# demeter.net
KiCad netlist of a schematic drawn in EAGLE
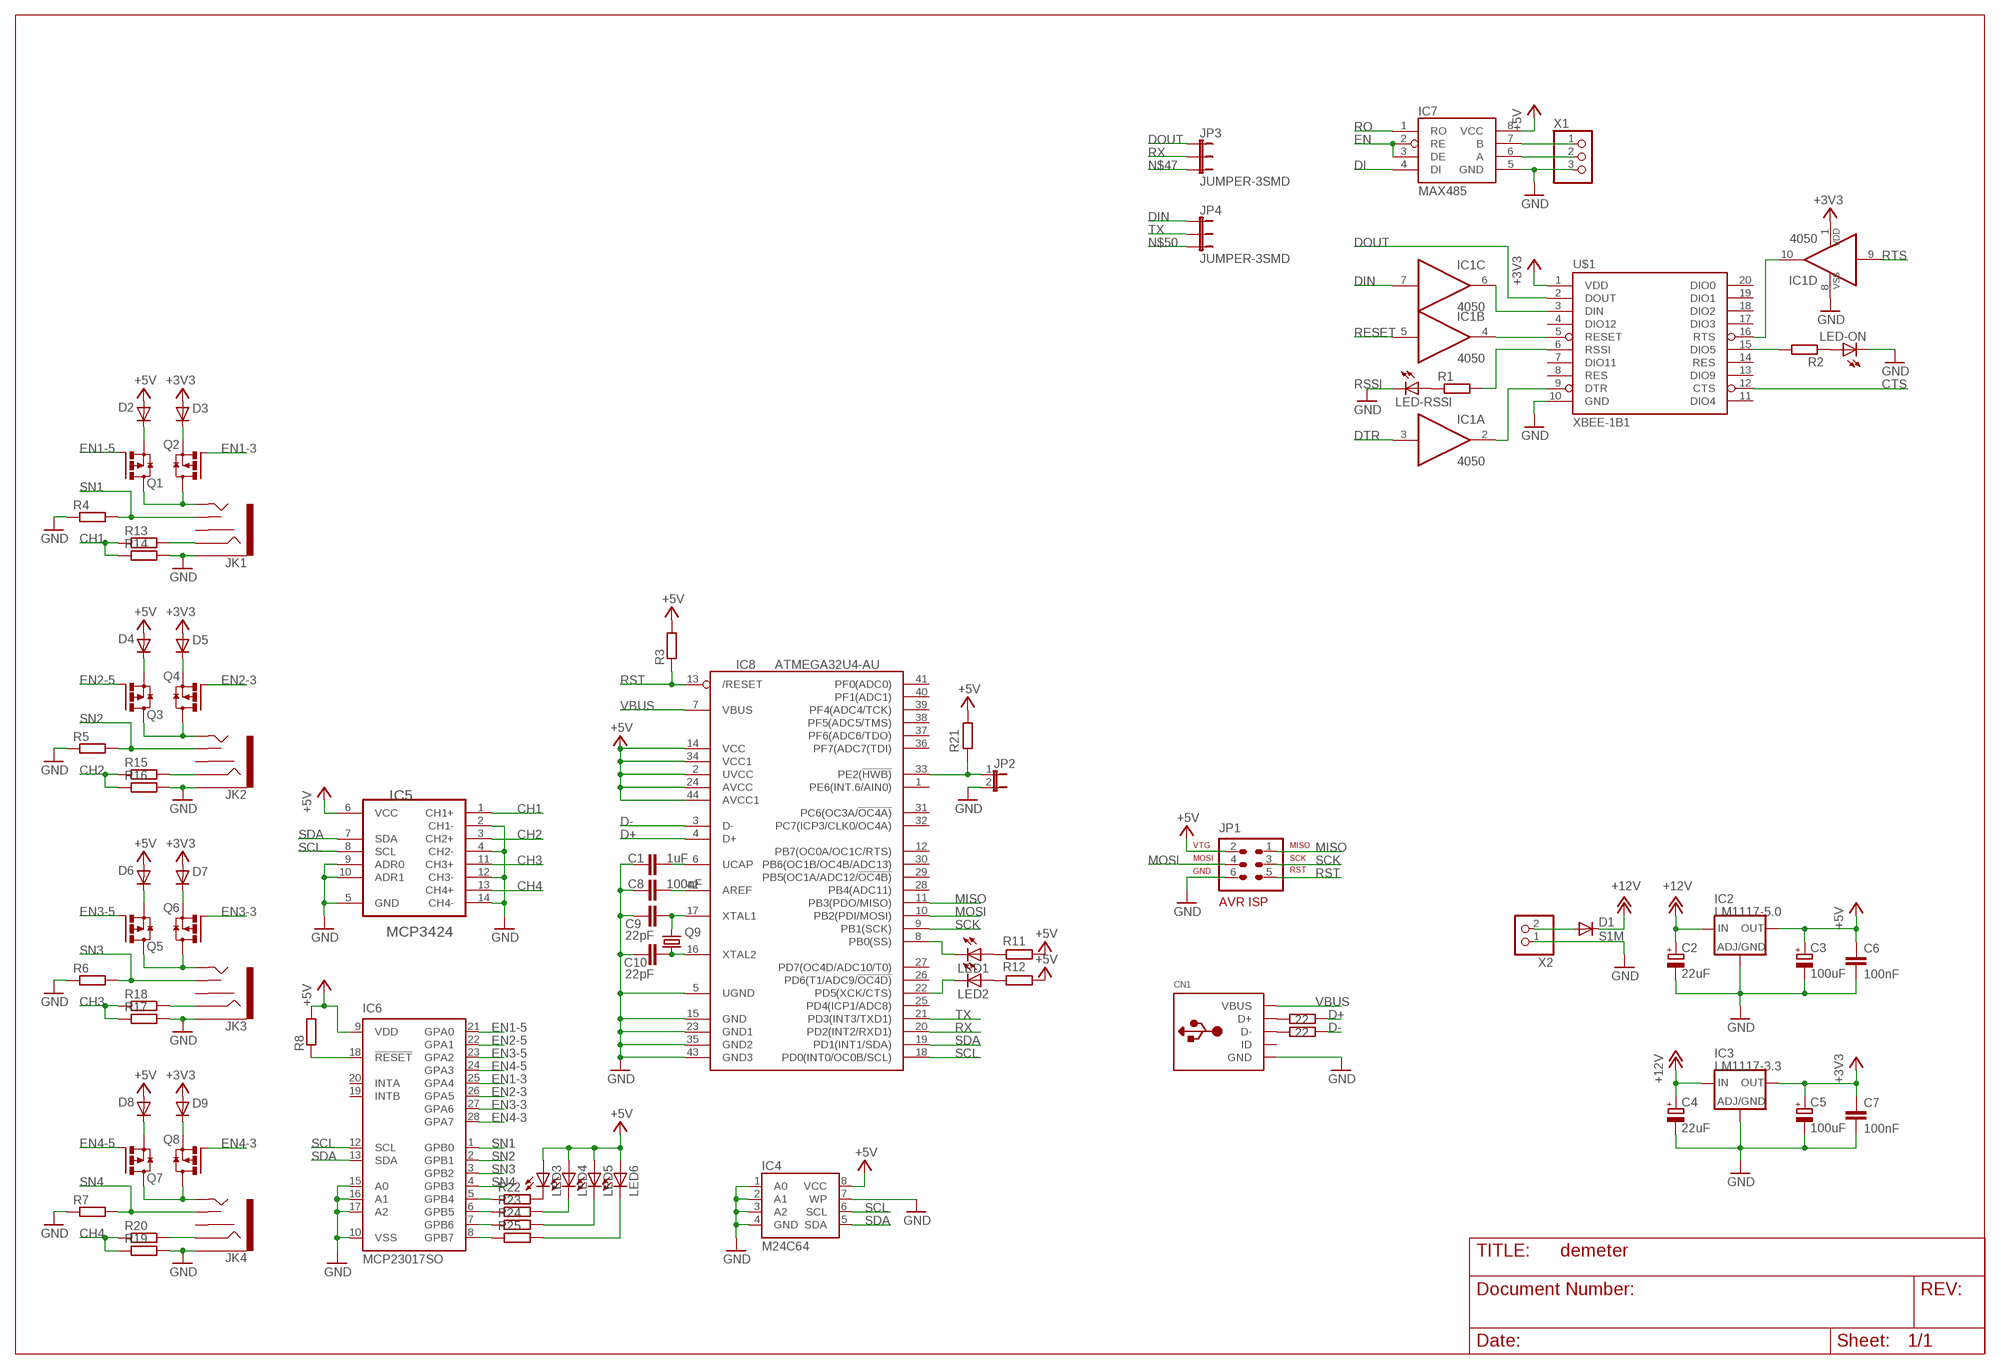
[diagram p0: schematic, sheet 1]

(export (version "E")
  (design (tool "Eeschema 10.0.6"))
  (components
    (comp (ref "C1")
      (value "1uF")
      (footprint "eagle-import:C0805K")
      (libsource (lib "eagle-import") (part "C-EUC0805K"))
    )
    (comp (ref "C2")
      (value "22uF")
      (footprint "eagle-import:PANASONIC_D")
      (libsource (lib "eagle-import") (part "CPOL-EUPD"))
    )
    (comp (ref "C3")
      (value "100uF")
      (footprint "eagle-import:PANASONIC_D")
      (libsource (lib "eagle-import") (part "CPOL-EUPD"))
    )
    (comp (ref "C4")
      (value "22uF")
      (footprint "eagle-import:PANASONIC_D")
      (libsource (lib "eagle-import") (part "CPOL-EUPD"))
    )
    (comp (ref "C5")
      (value "100uF")
      (footprint "eagle-import:PANASONIC_D")
      (libsource (lib "eagle-import") (part "CPOL-EUPD"))
    )
    (comp (ref "C6")
      (value "100nF")
      (footprint "eagle-import:C0805K")
      (libsource (lib "eagle-import") (part "C-EUC0805K"))
    )
    (comp (ref "C7")
      (value "100nF")
      (footprint "eagle-import:C0805K")
      (libsource (lib "eagle-import") (part "C-EUC0805K"))
    )
    (comp (ref "C8")
      (value "100nF")
      (footprint "eagle-import:C0805K")
      (libsource (lib "eagle-import") (part "C-EUC0805K"))
    )
    (comp (ref "C9")
      (value "22pF")
      (footprint "eagle-import:C0805K")
      (libsource (lib "eagle-import") (part "C-EUC0805K"))
    )
    (comp (ref "C10")
      (value "22pF")
      (footprint "eagle-import:C0805K")
      (libsource (lib "eagle-import") (part "C-EUC0805K"))
    )
    (comp (ref "CN1")
      (value "USBMINIB")
      (footprint "eagle-import:USB-MINIB")
      (libsource (lib "eagle-import") (part "USBMINIB"))
    )
    (comp (ref "D1")
      (value "S1M")
      (footprint "eagle-import:DO-214AC")
      (libsource (lib "eagle-import") (part "S1M"))
    )
    (comp (ref "D2")
      (value "MBR0520")
      (footprint "eagle-import:SOD123")
      (libsource (lib "eagle-import") (part "MBR0520"))
    )
    (comp (ref "D3")
      (value "MBR0520")
      (footprint "eagle-import:SOD123")
      (libsource (lib "eagle-import") (part "MBR0520"))
    )
    (comp (ref "D4")
      (value "MBR0520")
      (footprint "eagle-import:SOD123")
      (libsource (lib "eagle-import") (part "MBR0520"))
    )
    (comp (ref "D5")
      (value "MBR0520")
      (footprint "eagle-import:SOD123")
      (libsource (lib "eagle-import") (part "MBR0520"))
    )
    (comp (ref "D6")
      (value "MBR0520")
      (footprint "eagle-import:SOD123")
      (libsource (lib "eagle-import") (part "MBR0520"))
    )
    (comp (ref "D7")
      (value "MBR0520")
      (footprint "eagle-import:SOD123")
      (libsource (lib "eagle-import") (part "MBR0520"))
    )
    (comp (ref "D8")
      (value "MBR0520")
      (footprint "eagle-import:SOD123")
      (libsource (lib "eagle-import") (part "MBR0520"))
    )
    (comp (ref "D9")
      (value "MBR0520")
      (footprint "eagle-import:SOD123")
      (libsource (lib "eagle-import") (part "MBR0520"))
    )
    (comp (ref "IC1")
      (value "4050")
      (footprint "eagle-import:SO16")
      (libsource (lib "eagle-import") (part "4050D"))
    )
    (comp (ref "IC2")
      (value "LM1117-5.0")
      (footprint "eagle-import:DPACK")
      (libsource (lib "eagle-import") (part "LM1117DT"))
    )
    (comp (ref "IC3")
      (value "LM1117-3.3")
      (footprint "eagle-import:DPACK")
      (libsource (lib "eagle-import") (part "LM1117DT"))
    )
    (comp (ref "IC4")
      (value "M24C64")
      (footprint "eagle-import:SO08")
      (libsource (lib "eagle-import") (part "AT24C"))
    )
    (comp (ref "IC5")
      (value "MCP3424")
      (footprint "eagle-import:SO14")
      (fields (field (name "MPN") "MCP3424-E/SL"))
      (libsource (lib "eagle-import") (part "MCP3424"))
    )
    (comp (ref "IC6")
      (value "MCP23017SO")
      (footprint "eagle-import:SO28W")
      (fields (field (name "MF") "MICROCHIP") (field (name "MPN") "MCP23017-E/SO"))
      (libsource (lib "eagle-import") (part "MCP23017SO"))
    )
    (comp (ref "IC7")
      (value "MAX485")
      (footprint "eagle-import:SO08")
      (libsource (lib "eagle-import") (part "MAX485"))
    )
    (comp (ref "IC8")
      (value "ATMEGA32U4-AU")
      (footprint "eagle-import:TQFP44")
      (libsource (lib "eagle-import") (part "ATMEGA32U4-AU"))
    )
    (comp (ref "JK1")
      (value "AUDIO-JACK2PTH")
      (footprint "eagle-import:AUDIO-JACK")
      (libsource (lib "eagle-import") (part "AUDIO-JACK2PTH"))
    )
    (comp (ref "JK2")
      (value "AUDIO-JACK2PTH")
      (footprint "eagle-import:AUDIO-JACK")
      (libsource (lib "eagle-import") (part "AUDIO-JACK2PTH"))
    )
    (comp (ref "JK3")
      (value "AUDIO-JACK2PTH")
      (footprint "eagle-import:AUDIO-JACK")
      (libsource (lib "eagle-import") (part "AUDIO-JACK2PTH"))
    )
    (comp (ref "JK4")
      (value "AUDIO-JACK2PTH")
      (footprint "eagle-import:AUDIO-JACK")
      (libsource (lib "eagle-import") (part "AUDIO-JACK2PTH"))
    )
    (comp (ref "JP1")
      (value "AVR-ISP-6")
      (footprint "eagle-import:AVR-ISP-6")
      (libsource (lib "eagle-import") (part "AVR-ISP-6"))
    )
    (comp (ref "JP2")
      (value "JUMPER-2SMD-NO")
      (footprint "eagle-import:SJ_2S-NO")
      (libsource (lib "eagle-import") (part "JUMPER-2SMD-NO"))
    )
    (comp (ref "JP3")
      (value "JUMPER-3SMD")
      (footprint "eagle-import:SJ_3")
      (libsource (lib "eagle-import") (part "JUMPER-3SMD"))
    )
    (comp (ref "JP4")
      (value "JUMPER-3SMD")
      (footprint "eagle-import:SJ_3")
      (libsource (lib "eagle-import") (part "JUMPER-3SMD"))
    )
    (comp (ref "LED-ON")
      (value "LED3MM")
      (footprint "eagle-import:LED3MM")
      (libsource (lib "eagle-import") (part "LED3MM"))
    )
    (comp (ref "LED-RSSI")
      (value "LED3MM")
      (footprint "eagle-import:LED3MM")
      (libsource (lib "eagle-import") (part "LED3MM"))
    )
    (comp (ref "LED1")
      (value "LED0805")
      (footprint "eagle-import:CHIP-LED0805")
      (libsource (lib "eagle-import") (part "mark_2_LED0805"))
    )
    (comp (ref "LED2")
      (value "LED0805")
      (footprint "eagle-import:CHIP-LED0805")
      (libsource (lib "eagle-import") (part "mark_2_LED0805"))
    )
    (comp (ref "LED3")
      (value "LED0805")
      (footprint "eagle-import:CHIP-LED0805")
      (libsource (lib "eagle-import") (part "mark_2_LED0805"))
    )
    (comp (ref "LED4")
      (value "LED0805")
      (footprint "eagle-import:CHIP-LED0805")
      (libsource (lib "eagle-import") (part "mark_2_LED0805"))
    )
    (comp (ref "LED5")
      (value "LED0805")
      (footprint "eagle-import:CHIP-LED0805")
      (libsource (lib "eagle-import") (part "mark_2_LED0805"))
    )
    (comp (ref "LED6")
      (value "LED0805")
      (footprint "eagle-import:CHIP-LED0805")
      (libsource (lib "eagle-import") (part "mark_2_LED0805"))
    )
    (comp (ref "Q1")
      (value "IRLML6402")
      (footprint "eagle-import:SOT23")
      (libsource (lib "eagle-import") (part "IRLML6402"))
    )
    (comp (ref "Q2")
      (value "IRLML6402")
      (footprint "eagle-import:SOT23")
      (libsource (lib "eagle-import") (part "IRLML6402"))
    )
    (comp (ref "Q3")
      (value "IRLML6402")
      (footprint "eagle-import:SOT23")
      (libsource (lib "eagle-import") (part "IRLML6402"))
    )
    (comp (ref "Q4")
      (value "IRLML6402")
      (footprint "eagle-import:SOT23")
      (libsource (lib "eagle-import") (part "IRLML6402"))
    )
    (comp (ref "Q5")
      (value "IRLML6402")
      (footprint "eagle-import:SOT23")
      (libsource (lib "eagle-import") (part "IRLML6402"))
    )
    (comp (ref "Q6")
      (value "IRLML6402")
      (footprint "eagle-import:SOT23")
      (libsource (lib "eagle-import") (part "IRLML6402"))
    )
    (comp (ref "Q7")
      (value "IRLML6402")
      (footprint "eagle-import:SOT23")
      (libsource (lib "eagle-import") (part "IRLML6402"))
    )
    (comp (ref "Q8")
      (value "IRLML6402")
      (footprint "eagle-import:SOT23")
      (libsource (lib "eagle-import") (part "IRLML6402"))
    )
    (comp (ref "Q9")
      (value "CRYSTALHC49UP")
      (footprint "eagle-import:HC49UP")
      (libsource (lib "eagle-import") (part "CRYSTALHC49UP"))
    )
    (comp (ref "R1")
      (value "R-EU_R0805")
      (footprint "eagle-import:R0805")
      (libsource (lib "eagle-import") (part "R-EU_R0805"))
    )
    (comp (ref "R2")
      (value "R-EU_R0805")
      (footprint "eagle-import:R0805")
      (libsource (lib "eagle-import") (part "R-EU_R0805"))
    )
    (comp (ref "R3")
      (value "R-EU_R0805")
      (footprint "eagle-import:R0805")
      (libsource (lib "eagle-import") (part "R-EU_R0805"))
    )
    (comp (ref "R4")
      (value "R-EU_R0805")
      (footprint "eagle-import:R0805")
      (libsource (lib "eagle-import") (part "R-EU_R0805"))
    )
    (comp (ref "R5")
      (value "R-EU_R0805")
      (footprint "eagle-import:R0805")
      (libsource (lib "eagle-import") (part "R-EU_R0805"))
    )
    (comp (ref "R6")
      (value "R-EU_R0805")
      (footprint "eagle-import:R0805")
      (libsource (lib "eagle-import") (part "R-EU_R0805"))
    )
    (comp (ref "R7")
      (value "R-EU_R0805")
      (footprint "eagle-import:R0805")
      (libsource (lib "eagle-import") (part "R-EU_R0805"))
    )
    (comp (ref "R8")
      (value "R-EU_R0805")
      (footprint "eagle-import:R0805")
      (libsource (lib "eagle-import") (part "R-EU_R0805"))
    )
    (comp (ref "R9")
      (value "22")
      (footprint "eagle-import:R0805")
      (libsource (lib "eagle-import") (part "R-EU_R0805"))
    )
    (comp (ref "R10")
      (value "22")
      (footprint "eagle-import:R0805")
      (libsource (lib "eagle-import") (part "R-EU_R0805"))
    )
    (comp (ref "R11")
      (value "R-EU_R0805")
      (footprint "eagle-import:R0805")
      (libsource (lib "eagle-import") (part "R-EU_R0805"))
    )
    (comp (ref "R12")
      (value "R-EU_R0805")
      (footprint "eagle-import:R0805")
      (libsource (lib "eagle-import") (part "R-EU_R0805"))
    )
    (comp (ref "R13")
      (value "R-EU_R0805")
      (footprint "eagle-import:R0805")
      (libsource (lib "eagle-import") (part "R-EU_R0805"))
    )
    (comp (ref "R14")
      (value "R-EU_R0805")
      (footprint "eagle-import:R0805")
      (libsource (lib "eagle-import") (part "R-EU_R0805"))
    )
    (comp (ref "R15")
      (value "R-EU_R0805")
      (footprint "eagle-import:R0805")
      (libsource (lib "eagle-import") (part "R-EU_R0805"))
    )
    (comp (ref "R16")
      (value "R-EU_R0805")
      (footprint "eagle-import:R0805")
      (libsource (lib "eagle-import") (part "R-EU_R0805"))
    )
    (comp (ref "R17")
      (value "R-EU_R0805")
      (footprint "eagle-import:R0805")
      (libsource (lib "eagle-import") (part "R-EU_R0805"))
    )
    (comp (ref "R18")
      (value "R-EU_R0805")
      (footprint "eagle-import:R0805")
      (libsource (lib "eagle-import") (part "R-EU_R0805"))
    )
    (comp (ref "R19")
      (value "R-EU_R0805")
      (footprint "eagle-import:R0805")
      (libsource (lib "eagle-import") (part "R-EU_R0805"))
    )
    (comp (ref "R20")
      (value "R-EU_R0805")
      (footprint "eagle-import:R0805")
      (libsource (lib "eagle-import") (part "R-EU_R0805"))
    )
    (comp (ref "R21")
      (value "R-EU_R0805")
      (footprint "eagle-import:R0805")
      (libsource (lib "eagle-import") (part "R-EU_R0805"))
    )
    (comp (ref "R22")
      (value "R-EU_R0805")
      (footprint "eagle-import:R0805")
      (libsource (lib "eagle-import") (part "R-EU_R0805"))
    )
    (comp (ref "R23")
      (value "R-EU_R0805")
      (footprint "eagle-import:R0805")
      (libsource (lib "eagle-import") (part "R-EU_R0805"))
    )
    (comp (ref "R24")
      (value "R-EU_R0805")
      (footprint "eagle-import:R0805")
      (libsource (lib "eagle-import") (part "R-EU_R0805"))
    )
    (comp (ref "R25")
      (value "R-EU_R0805")
      (footprint "eagle-import:R0805")
      (libsource (lib "eagle-import") (part "R-EU_R0805"))
    )
    (comp (ref "U$1")
      (value "XBEE-1B1")
      (footprint "eagle-import:XBEE-1")
      (libsource (lib "eagle-import") (part "XBEE-1B1"))
    )
    (comp (ref "X1")
      (value "W237-103")
      (footprint "eagle-import:W237-103")
      (libsource (lib "eagle-import") (part "W237-103"))
    )
    (comp (ref "X2")
      (value "W237-102")
      (footprint "eagle-import:W237-102")
      (libsource (lib "eagle-import") (part "W237-102"))
    )
  )
  (nets
    (net (code "1") (name "+3V3") (class "Default")
      (node (ref "C5") (pin "+") (pinfunction "+_+") (pintype "passive"))
      (node (ref "C7") (pin "1") (pinfunction "1_1") (pintype "passive"))
      (node (ref "D3") (pin "A") (pinfunction "A_A") (pintype "passive"))
      (node (ref "D5") (pin "A") (pinfunction "A_A") (pintype "passive"))
      (node (ref "D7") (pin "A") (pinfunction "A_A") (pintype "passive"))
      (node (ref "D9") (pin "A") (pinfunction "A_A") (pintype "passive"))
      (node (ref "IC1") (pin "1") (pinfunction "VDD_1") (pintype "power_in"))
      (node (ref "IC3") (pin "4") (pinfunction "OUT_4") (pintype "passive"))
      (node (ref "U$1") (pin "1") (pinfunction "VDD_1") (pintype "power_in"))
    )
    (net (code "2") (name "+5V") (class "Default")
      (node (ref "C3") (pin "+") (pinfunction "+_+") (pintype "passive"))
      (node (ref "C6") (pin "1") (pinfunction "1_1") (pintype "passive"))
      (node (ref "D2") (pin "A") (pinfunction "A_A") (pintype "passive"))
      (node (ref "D4") (pin "A") (pinfunction "A_A") (pintype "passive"))
      (node (ref "D6") (pin "A") (pinfunction "A_A") (pintype "passive"))
      (node (ref "D8") (pin "A") (pinfunction "A_A") (pintype "passive"))
      (node (ref "IC2") (pin "4") (pinfunction "OUT_4") (pintype "passive"))
      (node (ref "IC4") (pin "8") (pinfunction "VCC_8") (pintype "power_in"))
      (node (ref "IC5") (pin "6") (pinfunction "VCC_6") (pintype "power_in"))
      (node (ref "IC6") (pin "9") (pinfunction "VDD_9") (pintype "power_in"))
      (node (ref "IC7") (pin "8") (pinfunction "VCC_8") (pintype "bidirectional"))
      (node (ref "IC8") (pin "14") (pinfunction "VCC_14") (pintype "bidirectional"))
      (node (ref "IC8") (pin "2") (pinfunction "UVCC_2") (pintype "bidirectional"))
      (node (ref "IC8") (pin "24") (pinfunction "AVCC_24") (pintype "bidirectional"))
      (node (ref "IC8") (pin "34") (pinfunction "VCC1_34") (pintype "bidirectional"))
      (node (ref "IC8") (pin "44") (pinfunction "AVCC1_44") (pintype "bidirectional"))
      (node (ref "JP1") (pin "2") (pinfunction "VTG_2") (pintype "passive"))
      (node (ref "LED3") (pin "A") (pinfunction "A_A") (pintype "passive"))
      (node (ref "LED4") (pin "A") (pinfunction "A_A") (pintype "passive"))
      (node (ref "LED5") (pin "A") (pinfunction "A_A") (pintype "passive"))
      (node (ref "LED6") (pin "A") (pinfunction "A_A") (pintype "passive"))
      (node (ref "R11") (pin "1") (pinfunction "1_1") (pintype "passive"))
      (node (ref "R12") (pin "1") (pinfunction "1_1") (pintype "passive"))
      (node (ref "R21") (pin "1") (pinfunction "1_1") (pintype "passive"))
      (node (ref "R3") (pin "2") (pinfunction "2_2") (pintype "passive"))
      (node (ref "R8") (pin "2") (pinfunction "2_2") (pintype "passive"))
    )
    (net (code "3") (name "+12V") (class "Default")
      (node (ref "C2") (pin "+") (pinfunction "+_+") (pintype "passive"))
      (node (ref "C4") (pin "+") (pinfunction "+_+") (pintype "passive"))
      (node (ref "D1") (pin "C") (pinfunction "C_C") (pintype "passive"))
      (node (ref "IC2") (pin "3") (pinfunction "IN_3") (pintype "input"))
      (node (ref "IC3") (pin "3") (pinfunction "IN_3") (pintype "input"))
    )
    (net (code "4") (name "/CH1") (class "Default")
      (node (ref "IC5") (pin "1") (pinfunction "CH1+_1") (pintype "input"))
      (node (ref "R13") (pin "1") (pinfunction "1_1") (pintype "passive"))
      (node (ref "R14") (pin "1") (pinfunction "1_1") (pintype "passive"))
    )
    (net (code "5") (name "/CH2") (class "Default")
      (node (ref "IC5") (pin "3") (pinfunction "CH2+_3") (pintype "input"))
      (node (ref "R15") (pin "1") (pinfunction "1_1") (pintype "passive"))
      (node (ref "R16") (pin "1") (pinfunction "1_1") (pintype "passive"))
    )
    (net (code "6") (name "/CH3") (class "Default")
      (node (ref "IC5") (pin "11") (pinfunction "CH3+_11") (pintype "input"))
      (node (ref "R17") (pin "1") (pinfunction "1_1") (pintype "passive"))
      (node (ref "R18") (pin "1") (pinfunction "1_1") (pintype "passive"))
    )
    (net (code "7") (name "/CH4") (class "Default")
      (node (ref "IC5") (pin "13") (pinfunction "CH4+_13") (pintype "input"))
      (node (ref "R19") (pin "1") (pinfunction "1_1") (pintype "passive"))
      (node (ref "R20") (pin "1") (pinfunction "1_1") (pintype "passive"))
    )
    (net (code "8") (name "/CTS") (class "Default")
      (node (ref "U$1") (pin "12") (pinfunction "CTS_12") (pintype "output"))
    )
    (net (code "9") (name "/D+") (class "Default")
      (node (ref "IC8") (pin "4") (pinfunction "D+_4") (pintype "bidirectional"))
      (node (ref "R9") (pin "1") (pinfunction "1_1") (pintype "passive"))
    )
    (net (code "10") (name "/D-") (class "Default")
      (node (ref "IC8") (pin "3") (pinfunction "D-_3") (pintype "bidirectional"))
      (node (ref "R10") (pin "1") (pinfunction "1_1") (pintype "passive"))
    )
    (net (code "11") (name "/DI") (class "Default")
      (node (ref "IC7") (pin "4") (pinfunction "DI_4") (pintype "bidirectional"))
    )
    (net (code "12") (name "/DIN") (class "Default")
      (node (ref "IC1") (pin "7") (pinfunction "I_7") (pintype "input"))
      (node (ref "JP4") (pin "1") (pinfunction "1_1") (pintype "passive"))
    )
    (net (code "13") (name "/DOUT") (class "Default")
      (node (ref "JP3") (pin "1") (pinfunction "1_1") (pintype "passive"))
      (node (ref "U$1") (pin "2") (pinfunction "DOUT_2") (pintype "output"))
    )
    (net (code "14") (name "/DTR") (class "Default")
      (node (ref "IC1") (pin "3") (pinfunction "I_3") (pintype "input"))
    )
    (net (code "15") (name "/EN") (class "Default")
      (node (ref "IC7") (pin "2") (pinfunction "RE_2") (pintype "bidirectional"))
      (node (ref "IC7") (pin "3") (pinfunction "DE_3") (pintype "bidirectional"))
    )
    (net (code "16") (name "/EN1-3") (class "Default")
      (node (ref "IC6") (pin "25") (pinfunction "GPA4_25") (pintype "bidirectional"))
      (node (ref "Q2") (pin "1") (pinfunction "G_1") (pintype "passive"))
    )
    (net (code "17") (name "/EN1-5") (class "Default")
      (node (ref "IC6") (pin "21") (pinfunction "GPA0_21") (pintype "bidirectional"))
      (node (ref "Q1") (pin "1") (pinfunction "G_1") (pintype "passive"))
    )
    (net (code "18") (name "/EN2-3") (class "Default")
      (node (ref "IC6") (pin "26") (pinfunction "GPA5_26") (pintype "bidirectional"))
      (node (ref "Q4") (pin "1") (pinfunction "G_1") (pintype "passive"))
    )
    (net (code "19") (name "/EN2-5") (class "Default")
      (node (ref "IC6") (pin "22") (pinfunction "GPA1_22") (pintype "bidirectional"))
      (node (ref "Q3") (pin "1") (pinfunction "G_1") (pintype "passive"))
    )
    (net (code "20") (name "/EN3-3") (class "Default")
      (node (ref "IC6") (pin "27") (pinfunction "GPA6_27") (pintype "bidirectional"))
      (node (ref "Q6") (pin "1") (pinfunction "G_1") (pintype "passive"))
    )
    (net (code "21") (name "/EN3-5") (class "Default")
      (node (ref "IC6") (pin "23") (pinfunction "GPA2_23") (pintype "bidirectional"))
      (node (ref "Q5") (pin "1") (pinfunction "G_1") (pintype "passive"))
    )
    (net (code "22") (name "/EN4-3") (class "Default")
      (node (ref "IC6") (pin "28") (pinfunction "GPA7_28") (pintype "bidirectional"))
      (node (ref "Q8") (pin "1") (pinfunction "G_1") (pintype "passive"))
    )
    (net (code "23") (name "/EN4-5") (class "Default")
      (node (ref "IC6") (pin "24") (pinfunction "GPA3_24") (pintype "bidirectional"))
      (node (ref "Q7") (pin "1") (pinfunction "G_1") (pintype "passive"))
    )
    (net (code "24") (name "/MISO") (class "Default")
      (node (ref "IC8") (pin "11") (pinfunction "PB3(PDO/MISO)_11") (pintype "bidirectional"))
      (node (ref "JP1") (pin "1") (pinfunction "MISO_1") (pintype "passive"))
    )
    (net (code "25") (name "/MOSI") (class "Default")
      (node (ref "IC8") (pin "10") (pinfunction "PB2(PDI/MOSI)_10") (pintype "bidirectional"))
      (node (ref "JP1") (pin "4") (pinfunction "MOSI_4") (pintype "passive"))
    )
    (net (code "26") (name "/N$47") (class "Default")
      (node (ref "JP3") (pin "3") (pinfunction "3_3") (pintype "passive"))
    )
    (net (code "27") (name "/N$50") (class "Default")
      (node (ref "JP4") (pin "3") (pinfunction "3_3") (pintype "passive"))
    )
    (net (code "28") (name "/RESET") (class "Default")
      (node (ref "IC1") (pin "5") (pinfunction "I_5") (pintype "input"))
    )
    (net (code "29") (name "/RO") (class "Default")
      (node (ref "IC7") (pin "1") (pinfunction "RO_1") (pintype "bidirectional"))
    )
    (net (code "30") (name "/RSSI") (class "Default")
      (node (ref "R1") (pin "2") (pinfunction "2_2") (pintype "passive"))
      (node (ref "U$1") (pin "6") (pinfunction "RSSI_6") (pintype "bidirectional"))
    )
    (net (code "31") (name "/RST") (class "Default")
      (node (ref "IC8") (pin "13") (pinfunction "/RESET_13") (pintype "bidirectional"))
      (node (ref "JP1") (pin "5") (pinfunction "RST_5") (pintype "passive"))
      (node (ref "R3") (pin "1") (pinfunction "1_1") (pintype "passive"))
    )
    (net (code "32") (name "/RTS") (class "Default")
      (node (ref "IC1") (pin "9") (pinfunction "I_9") (pintype "input"))
    )
    (net (code "33") (name "/RX") (class "Default")
      (node (ref "IC8") (pin "20") (pinfunction "PD2(INT2/RXD1)_20") (pintype "bidirectional"))
      (node (ref "JP3") (pin "2") (pinfunction "2_2") (pintype "passive"))
    )
    (net (code "34") (name "/SCK") (class "Default")
      (node (ref "IC8") (pin "9") (pinfunction "PB1(SCK)_9") (pintype "bidirectional"))
      (node (ref "JP1") (pin "3") (pinfunction "SCK_3") (pintype "passive"))
    )
    (net (code "35") (name "/SCL") (class "Default")
      (node (ref "IC4") (pin "6") (pinfunction "SCL_6") (pintype "bidirectional"))
      (node (ref "IC5") (pin "8") (pinfunction "SCL_8") (pintype "input"))
      (node (ref "IC6") (pin "12") (pinfunction "SCL_12") (pintype "input"))
      (node (ref "IC8") (pin "18") (pinfunction "PD0(INT0/OC0B/SCL)_18") (pintype "bidirectional"))
    )
    (net (code "36") (name "/SDA") (class "Default")
      (node (ref "IC4") (pin "5") (pinfunction "SDA_5") (pintype "bidirectional"))
      (node (ref "IC5") (pin "7") (pinfunction "SDA_7") (pintype "bidirectional"))
      (node (ref "IC6") (pin "13") (pinfunction "SDA_13") (pintype "bidirectional"))
      (node (ref "IC8") (pin "19") (pinfunction "PD1(INT1/SDA)_19") (pintype "bidirectional"))
    )
    (net (code "37") (name "/SN1") (class "Default")
      (node (ref "IC6") (pin "1") (pinfunction "GPB0_1") (pintype "bidirectional"))
      (node (ref "JK1") (pin "TSH") (pinfunction "TSH_TSH") (pintype "bidirectional"))
      (node (ref "R4") (pin "2") (pinfunction "2_2") (pintype "passive"))
    )
    (net (code "38") (name "/SN2") (class "Default")
      (node (ref "IC6") (pin "2") (pinfunction "GPB1_2") (pintype "bidirectional"))
      (node (ref "JK2") (pin "TSH") (pinfunction "TSH_TSH") (pintype "bidirectional"))
      (node (ref "R5") (pin "2") (pinfunction "2_2") (pintype "passive"))
    )
    (net (code "39") (name "/SN3") (class "Default")
      (node (ref "IC6") (pin "3") (pinfunction "GPB2_3") (pintype "bidirectional"))
      (node (ref "JK3") (pin "TSH") (pinfunction "TSH_TSH") (pintype "bidirectional"))
      (node (ref "R6") (pin "2") (pinfunction "2_2") (pintype "passive"))
    )
    (net (code "40") (name "/SN4") (class "Default")
      (node (ref "IC6") (pin "4") (pinfunction "GPB3_4") (pintype "bidirectional"))
      (node (ref "JK4") (pin "TSH") (pinfunction "TSH_TSH") (pintype "bidirectional"))
      (node (ref "R7") (pin "2") (pinfunction "2_2") (pintype "passive"))
    )
    (net (code "41") (name "/TX") (class "Default")
      (node (ref "IC8") (pin "21") (pinfunction "PD3(INT3/TXD1)_21") (pintype "bidirectional"))
      (node (ref "JP4") (pin "2") (pinfunction "2_2") (pintype "passive"))
    )
    (net (code "42") (name "/VBUS") (class "Default")
      (node (ref "CN1") (pin "VBUS") (pinfunction "VBUS_VBUS") (pintype "power_in"))
      (node (ref "IC8") (pin "7") (pinfunction "VBUS_7") (pintype "bidirectional"))
    )
    (net (code "43") (name "GND") (class "Default")
      (node (ref "C1") (pin "2") (pinfunction "2_2") (pintype "passive"))
      (node (ref "C10") (pin "2") (pinfunction "2_2") (pintype "passive"))
      (node (ref "C2") (pin "-") (pinfunction "-_-") (pintype "passive"))
      (node (ref "C3") (pin "-") (pinfunction "-_-") (pintype "passive"))
      (node (ref "C4") (pin "-") (pinfunction "-_-") (pintype "passive"))
      (node (ref "C5") (pin "-") (pinfunction "-_-") (pintype "passive"))
      (node (ref "C6") (pin "2") (pinfunction "2_2") (pintype "passive"))
      (node (ref "C7") (pin "2") (pinfunction "2_2") (pintype "passive"))
      (node (ref "C8") (pin "2") (pinfunction "2_2") (pintype "passive"))
      (node (ref "C9") (pin "2") (pinfunction "2_2") (pintype "passive"))
      (node (ref "CN1") (pin "GND") (pinfunction "GND_GND") (pintype "power_in"))
      (node (ref "IC1") (pin "8") (pinfunction "VSS_8") (pintype "power_in"))
      (node (ref "IC2") (pin "1") (pinfunction "ADJ_1") (pintype "input"))
      (node (ref "IC3") (pin "1") (pinfunction "ADJ_1") (pintype "input"))
      (node (ref "IC4") (pin "1") (pinfunction "A0_1") (pintype "input"))
      (node (ref "IC4") (pin "2") (pinfunction "A1_2") (pintype "input"))
      (node (ref "IC4") (pin "3") (pinfunction "A2_3") (pintype "input"))
      (node (ref "IC4") (pin "4") (pinfunction "GND_4") (pintype "power_in"))
      (node (ref "IC4") (pin "7") (pinfunction "WP_7") (pintype "input"))
      (node (ref "IC5") (pin "10") (pinfunction "ADR1_10") (pintype "input"))
      (node (ref "IC5") (pin "12") (pinfunction "CH3-_12") (pintype "input"))
      (node (ref "IC5") (pin "14") (pinfunction "CH4-_14") (pintype "input"))
      (node (ref "IC5") (pin "2") (pinfunction "CH1-_2") (pintype "input"))
      (node (ref "IC5") (pin "4") (pinfunction "CH2-_4") (pintype "input"))
      (node (ref "IC5") (pin "5") (pinfunction "GND_5") (pintype "power_in"))
      (node (ref "IC5") (pin "9") (pinfunction "ADR0_9") (pintype "input"))
      (node (ref "IC6") (pin "10") (pinfunction "VSS_10") (pintype "power_in"))
      (node (ref "IC6") (pin "15") (pinfunction "A0_15") (pintype "input"))
      (node (ref "IC6") (pin "16") (pinfunction "A1_16") (pintype "input"))
      (node (ref "IC6") (pin "17") (pinfunction "A2_17") (pintype "input"))
      (node (ref "IC7") (pin "5") (pinfunction "GND_5") (pintype "bidirectional"))
      (node (ref "IC8") (pin "15") (pinfunction "GND_15") (pintype "bidirectional"))
      (node (ref "IC8") (pin "23") (pinfunction "GND1_23") (pintype "bidirectional"))
      (node (ref "IC8") (pin "35") (pinfunction "GND2_35") (pintype "bidirectional"))
      (node (ref "IC8") (pin "43") (pinfunction "GND3_43") (pintype "bidirectional"))
      (node (ref "IC8") (pin "5") (pinfunction "UGND_5") (pintype "bidirectional"))
      (node (ref "JK1") (pin "SLEEVE") (pinfunction "SLEEVE_SLEEVE") (pintype "bidirectional"))
      (node (ref "JK2") (pin "SLEEVE") (pinfunction "SLEEVE_SLEEVE") (pintype "bidirectional"))
      (node (ref "JK3") (pin "SLEEVE") (pinfunction "SLEEVE_SLEEVE") (pintype "bidirectional"))
      (node (ref "JK4") (pin "SLEEVE") (pinfunction "SLEEVE_SLEEVE") (pintype "bidirectional"))
      (node (ref "JP1") (pin "6") (pinfunction "GND_6") (pintype "passive"))
      (node (ref "JP2") (pin "2") (pinfunction "2_2") (pintype "passive"))
      (node (ref "LED-ON") (pin "K") (pinfunction "C_K") (pintype "passive"))
      (node (ref "LED-RSSI") (pin "K") (pinfunction "C_K") (pintype "passive"))
      (node (ref "R14") (pin "2") (pinfunction "2_2") (pintype "passive"))
      (node (ref "R16") (pin "2") (pinfunction "2_2") (pintype "passive"))
      (node (ref "R17") (pin "2") (pinfunction "2_2") (pintype "passive"))
      (node (ref "R19") (pin "2") (pinfunction "2_2") (pintype "passive"))
      (node (ref "R4") (pin "1") (pinfunction "1_1") (pintype "passive"))
      (node (ref "R5") (pin "1") (pinfunction "1_1") (pintype "passive"))
      (node (ref "R6") (pin "1") (pinfunction "1_1") (pintype "passive"))
      (node (ref "R7") (pin "1") (pinfunction "1_1") (pintype "passive"))
      (node (ref "U$1") (pin "10") (pinfunction "GND_10") (pintype "power_in"))
      (node (ref "X1") (pin "3") (pinfunction "3_3") (pintype "passive"))
      (node (ref "X2") (pin "1") (pinfunction "1_1") (pintype "passive"))
    )
    (net (code "44") (name "Net-(CN1-PadD+)") (class "Default")
      (node (ref "CN1") (pin "D+") (pinfunction "D+_D+") (pintype "bidirectional"))
      (node (ref "R9") (pin "2") (pinfunction "2_2") (pintype "passive"))
    )
    (net (code "45") (name "Net-(CN1-PadD-)") (class "Default")
      (node (ref "CN1") (pin "D-") (pinfunction "D-_D-") (pintype "bidirectional"))
      (node (ref "R10") (pin "2") (pinfunction "2_2") (pintype "passive"))
    )
    (net (code "46") (name "Net-(D1-PadA)") (class "Default")
      (node (ref "D1") (pin "A") (pinfunction "A_A") (pintype "passive"))
      (node (ref "X2") (pin "2") (pinfunction "2_2") (pintype "passive"))
    )
    (net (code "47") (name "Net-(IC1A-O)") (class "Default")
      (node (ref "IC1") (pin "2") (pinfunction "O_2") (pintype "output"))
      (node (ref "U$1") (pin "9") (pinfunction "DTR_9") (pintype "bidirectional"))
    )
    (net (code "48") (name "Net-(IC1B-O)") (class "Default")
      (node (ref "IC1") (pin "4") (pinfunction "O_4") (pintype "output"))
      (node (ref "U$1") (pin "5") (pinfunction "RESET_5") (pintype "input"))
    )
    (net (code "49") (name "Net-(IC1C-O)") (class "Default")
      (node (ref "IC1") (pin "6") (pinfunction "O_6") (pintype "output"))
      (node (ref "U$1") (pin "3") (pinfunction "DIN_3") (pintype "input"))
    )
    (net (code "50") (name "Net-(IC1D-O)") (class "Default")
      (node (ref "IC1") (pin "10") (pinfunction "O_10") (pintype "output"))
      (node (ref "U$1") (pin "16") (pinfunction "RTS_16") (pintype "input"))
    )
    (net (code "51") (name "Net-(IC6-GPB4)") (class "Default")
      (node (ref "IC6") (pin "5") (pinfunction "GPB4_5") (pintype "bidirectional"))
      (node (ref "R22") (pin "1") (pinfunction "1_1") (pintype "passive"))
    )
    (net (code "52") (name "Net-(IC6-GPB5)") (class "Default")
      (node (ref "IC6") (pin "6") (pinfunction "GPB5_6") (pintype "bidirectional"))
      (node (ref "R23") (pin "1") (pinfunction "1_1") (pintype "passive"))
    )
    (net (code "53") (name "Net-(IC6-GPB6)") (class "Default")
      (node (ref "IC6") (pin "7") (pinfunction "GPB6_7") (pintype "bidirectional"))
      (node (ref "R24") (pin "1") (pinfunction "1_1") (pintype "passive"))
    )
    (net (code "54") (name "Net-(IC6-GPB7)") (class "Default")
      (node (ref "IC6") (pin "8") (pinfunction "GPB7_8") (pintype "bidirectional"))
      (node (ref "R25") (pin "1") (pinfunction "1_1") (pintype "passive"))
    )
    (net (code "55") (name "Net-(IC6-~{RESET})") (class "Default")
      (node (ref "IC6") (pin "18") (pinfunction "~{RESET}_18") (pintype "input"))
      (node (ref "R8") (pin "1") (pinfunction "1_1") (pintype "passive"))
    )
    (net (code "56") (name "Net-(IC7-A)") (class "Default")
      (node (ref "IC7") (pin "6") (pinfunction "A_6") (pintype "bidirectional"))
      (node (ref "X1") (pin "2") (pinfunction "2_2") (pintype "passive"))
    )
    (net (code "57") (name "Net-(IC7-B)") (class "Default")
      (node (ref "IC7") (pin "7") (pinfunction "B_7") (pintype "bidirectional"))
      (node (ref "X1") (pin "1") (pinfunction "1_1") (pintype "passive"))
    )
    (net (code "58") (name "Net-(IC8-AREF)") (class "Default")
      (node (ref "C8") (pin "1") (pinfunction "1_1") (pintype "passive"))
      (node (ref "IC8") (pin "42") (pinfunction "AREF_42") (pintype "bidirectional"))
    )
    (net (code "59") (name "Net-(IC8-PB0(SS))") (class "Default")
      (node (ref "IC8") (pin "8") (pinfunction "PB0(SS)_8") (pintype "bidirectional"))
      (node (ref "LED1") (pin "C") (pinfunction "C_C") (pintype "passive"))
    )
    (net (code "60") (name "Net-(IC8-PD5(XCK{slash}CTS))") (class "Default")
      (node (ref "IC8") (pin "22") (pinfunction "PD5(XCK/CTS)_22") (pintype "bidirectional"))
      (node (ref "LED2") (pin "C") (pinfunction "C_C") (pintype "passive"))
    )
    (net (code "61") (name "Net-(IC8-PE2(~{HWB}))") (class "Default")
      (node (ref "IC8") (pin "33") (pinfunction "PE2(~{HWB})_33") (pintype "bidirectional"))
      (node (ref "JP2") (pin "1") (pinfunction "1_1") (pintype "passive"))
      (node (ref "R21") (pin "2") (pinfunction "2_2") (pintype "passive"))
    )
    (net (code "62") (name "Net-(IC8-UCAP)") (class "Default")
      (node (ref "C1") (pin "1") (pinfunction "1_1") (pintype "passive"))
      (node (ref "IC8") (pin "6") (pinfunction "UCAP_6") (pintype "bidirectional"))
    )
    (net (code "63") (name "Net-(IC8-XTAL1)") (class "Default")
      (node (ref "C9") (pin "1") (pinfunction "1_1") (pintype "passive"))
      (node (ref "IC8") (pin "17") (pinfunction "XTAL1_17") (pintype "bidirectional"))
      (node (ref "Q9") (pin "2") (pinfunction "2_2") (pintype "passive"))
    )
    (net (code "64") (name "Net-(IC8-XTAL2)") (class "Default")
      (node (ref "C10") (pin "1") (pinfunction "1_1") (pintype "passive"))
      (node (ref "IC8") (pin "16") (pinfunction "XTAL2_16") (pintype "bidirectional"))
      (node (ref "Q9") (pin "1") (pinfunction "1_1") (pintype "passive"))
    )
    (net (code "65") (name "Net-(JK1-PadRING)") (class "Default")
      (node (ref "JK1") (pin "RING") (pinfunction "RING_RING") (pintype "bidirectional"))
      (node (ref "R13") (pin "2") (pinfunction "2_2") (pintype "passive"))
    )
    (net (code "66") (name "Net-(JK2-PadRING)") (class "Default")
      (node (ref "JK2") (pin "RING") (pinfunction "RING_RING") (pintype "bidirectional"))
      (node (ref "R15") (pin "2") (pinfunction "2_2") (pintype "passive"))
    )
    (net (code "67") (name "Net-(JK3-PadRING)") (class "Default")
      (node (ref "JK3") (pin "RING") (pinfunction "RING_RING") (pintype "bidirectional"))
      (node (ref "R18") (pin "2") (pinfunction "2_2") (pintype "passive"))
    )
    (net (code "68") (name "Net-(JK4-PadRING)") (class "Default")
      (node (ref "JK4") (pin "RING") (pinfunction "RING_RING") (pintype "bidirectional"))
      (node (ref "R20") (pin "2") (pinfunction "2_2") (pintype "passive"))
    )
    (net (code "69") (name "Net-(LED-ON-PadA)") (class "Default")
      (node (ref "LED-ON") (pin "A") (pinfunction "A_A") (pintype "passive"))
      (node (ref "R2") (pin "1") (pinfunction "1_1") (pintype "passive"))
    )
    (net (code "70") (name "Net-(LED-RSSI-PadA)") (class "Default")
      (node (ref "LED-RSSI") (pin "A") (pinfunction "A_A") (pintype "passive"))
      (node (ref "R1") (pin "1") (pinfunction "1_1") (pintype "passive"))
    )
    (net (code "71") (name "Net-(LED1-PadA)") (class "Default")
      (node (ref "LED1") (pin "A") (pinfunction "A_A") (pintype "passive"))
      (node (ref "R11") (pin "2") (pinfunction "2_2") (pintype "passive"))
    )
    (net (code "72") (name "Net-(LED2-PadA)") (class "Default")
      (node (ref "LED2") (pin "A") (pinfunction "A_A") (pintype "passive"))
      (node (ref "R12") (pin "2") (pinfunction "2_2") (pintype "passive"))
    )
    (net (code "73") (name "Net-(LED3-PadC)") (class "Default")
      (node (ref "LED3") (pin "C") (pinfunction "C_C") (pintype "passive"))
      (node (ref "R22") (pin "2") (pinfunction "2_2") (pintype "passive"))
    )
    (net (code "74") (name "Net-(LED4-PadC)") (class "Default")
      (node (ref "LED4") (pin "C") (pinfunction "C_C") (pintype "passive"))
      (node (ref "R23") (pin "2") (pinfunction "2_2") (pintype "passive"))
    )
    (net (code "75") (name "Net-(LED5-PadC)") (class "Default")
      (node (ref "LED5") (pin "C") (pinfunction "C_C") (pintype "passive"))
      (node (ref "R24") (pin "2") (pinfunction "2_2") (pintype "passive"))
    )
    (net (code "76") (name "Net-(LED6-PadC)") (class "Default")
      (node (ref "LED6") (pin "C") (pinfunction "C_C") (pintype "passive"))
      (node (ref "R25") (pin "2") (pinfunction "2_2") (pintype "passive"))
    )
    (net (code "77") (name "Net-(Q1-D)") (class "Default")
      (node (ref "JK1") (pin "TIP") (pinfunction "TIP_TIP") (pintype "bidirectional"))
      (node (ref "Q1") (pin "3") (pinfunction "D_3") (pintype "passive"))
      (node (ref "Q2") (pin "3") (pinfunction "D_3") (pintype "passive"))
    )
    (net (code "78") (name "Net-(Q1-S)") (class "Default")
      (node (ref "D2") (pin "C") (pinfunction "C_C") (pintype "passive"))
      (node (ref "Q1") (pin "2") (pinfunction "S_2") (pintype "passive"))
    )
    (net (code "79") (name "Net-(Q2-S)") (class "Default")
      (node (ref "D3") (pin "C") (pinfunction "C_C") (pintype "passive"))
      (node (ref "Q2") (pin "2") (pinfunction "S_2") (pintype "passive"))
    )
    (net (code "80") (name "Net-(Q3-D)") (class "Default")
      (node (ref "JK2") (pin "TIP") (pinfunction "TIP_TIP") (pintype "bidirectional"))
      (node (ref "Q3") (pin "3") (pinfunction "D_3") (pintype "passive"))
      (node (ref "Q4") (pin "3") (pinfunction "D_3") (pintype "passive"))
    )
    (net (code "81") (name "Net-(Q3-S)") (class "Default")
      (node (ref "D4") (pin "C") (pinfunction "C_C") (pintype "passive"))
      (node (ref "Q3") (pin "2") (pinfunction "S_2") (pintype "passive"))
    )
    (net (code "82") (name "Net-(Q4-S)") (class "Default")
      (node (ref "D5") (pin "C") (pinfunction "C_C") (pintype "passive"))
      (node (ref "Q4") (pin "2") (pinfunction "S_2") (pintype "passive"))
    )
    (net (code "83") (name "Net-(Q5-D)") (class "Default")
      (node (ref "JK3") (pin "TIP") (pinfunction "TIP_TIP") (pintype "bidirectional"))
      (node (ref "Q5") (pin "3") (pinfunction "D_3") (pintype "passive"))
      (node (ref "Q6") (pin "3") (pinfunction "D_3") (pintype "passive"))
    )
    (net (code "84") (name "Net-(Q5-S)") (class "Default")
      (node (ref "D6") (pin "C") (pinfunction "C_C") (pintype "passive"))
      (node (ref "Q5") (pin "2") (pinfunction "S_2") (pintype "passive"))
    )
    (net (code "85") (name "Net-(Q6-S)") (class "Default")
      (node (ref "D7") (pin "C") (pinfunction "C_C") (pintype "passive"))
      (node (ref "Q6") (pin "2") (pinfunction "S_2") (pintype "passive"))
    )
    (net (code "86") (name "Net-(Q7-D)") (class "Default")
      (node (ref "JK4") (pin "TIP") (pinfunction "TIP_TIP") (pintype "bidirectional"))
      (node (ref "Q7") (pin "3") (pinfunction "D_3") (pintype "passive"))
      (node (ref "Q8") (pin "3") (pinfunction "D_3") (pintype "passive"))
    )
    (net (code "87") (name "Net-(Q7-S)") (class "Default")
      (node (ref "D8") (pin "C") (pinfunction "C_C") (pintype "passive"))
      (node (ref "Q7") (pin "2") (pinfunction "S_2") (pintype "passive"))
    )
    (net (code "88") (name "Net-(Q8-S)") (class "Default")
      (node (ref "D9") (pin "C") (pinfunction "C_C") (pintype "passive"))
      (node (ref "Q8") (pin "2") (pinfunction "S_2") (pintype "passive"))
    )
    (net (code "89") (name "Net-(U$1-DIO5)") (class "Default")
      (node (ref "R2") (pin "2") (pinfunction "2_2") (pintype "passive"))
      (node (ref "U$1") (pin "15") (pinfunction "DIO5_15") (pintype "bidirectional"))
    )
    (net (code "90") (name "unconnected-(CN1-PadID)") (class "Default")
      (node (ref "CN1") (pin "ID") (pinfunction "ID_ID") (pintype "bidirectional"))
    )
    (net (code "91") (name "unconnected-(IC6-INTA-Pad20)") (class "Default")
      (node (ref "IC6") (pin "20") (pinfunction "INTA_20") (pintype "output"))
    )
    (net (code "92") (name "unconnected-(IC6-INTB-Pad19)") (class "Default")
      (node (ref "IC6") (pin "19") (pinfunction "INTB_19") (pintype "output"))
    )
    (net (code "93") (name "unconnected-(IC8-PB4(ADC11)-Pad28)") (class "Default")
      (node (ref "IC8") (pin "28") (pinfunction "PB4(ADC11)_28") (pintype "bidirectional"))
    )
    (net (code "94") (name "unconnected-(IC8-PB5(OC1A{slash}ADC12{slash}~{OC4B})-Pad29)") (class "Default")
      (node (ref "IC8") (pin "29") (pinfunction "PB5(OC1A/ADC12/~{OC4B})_29") (pintype "bidirectional"))
    )
    (net (code "95") (name "unconnected-(IC8-PB6(OC1B{slash}OC4B{slash}ADC13)-Pad30)") (class "Default")
      (node (ref "IC8") (pin "30") (pinfunction "PB6(OC1B/OC4B/ADC13)_30") (pintype "bidirectional"))
    )
    (net (code "96") (name "unconnected-(IC8-PB7(OC0A{slash}OC1C{slash}RTS)-Pad12)") (class "Default")
      (node (ref "IC8") (pin "12") (pinfunction "PB7(OC0A/OC1C/RTS)_12") (pintype "bidirectional"))
    )
    (net (code "97") (name "unconnected-(IC8-PC6(OC3A{slash}~{OC4A})-Pad31)") (class "Default")
      (node (ref "IC8") (pin "31") (pinfunction "PC6(OC3A/~{OC4A})_31") (pintype "bidirectional"))
    )
    (net (code "98") (name "unconnected-(IC8-PC7(ICP3{slash}CLK0{slash}OC4A)-Pad32)") (class "Default")
      (node (ref "IC8") (pin "32") (pinfunction "PC7(ICP3/CLK0/OC4A)_32") (pintype "bidirectional"))
    )
    (net (code "99") (name "unconnected-(IC8-PD4(ICP1{slash}ADC8)-Pad25)") (class "Default")
      (node (ref "IC8") (pin "25") (pinfunction "PD4(ICP1/ADC8)_25") (pintype "bidirectional"))
    )
    (net (code "100") (name "unconnected-(IC8-PD6(T1{slash}ADC9{slash}~{OC4D})-Pad26)") (class "Default")
      (node (ref "IC8") (pin "26") (pinfunction "PD6(T1/ADC9/~{OC4D})_26") (pintype "bidirectional"))
    )
    (net (code "101") (name "unconnected-(IC8-PD7(OC4D{slash}ADC10{slash}T0)-Pad27)") (class "Default")
      (node (ref "IC8") (pin "27") (pinfunction "PD7(OC4D/ADC10/T0)_27") (pintype "bidirectional"))
    )
    (net (code "102") (name "unconnected-(IC8-PE6(INT.6{slash}AIN0)-Pad1)") (class "Default")
      (node (ref "IC8") (pin "1") (pinfunction "PE6(INT.6/AIN0)_1") (pintype "bidirectional"))
    )
    (net (code "103") (name "unconnected-(IC8-PF0(ADC0)-Pad41)") (class "Default")
      (node (ref "IC8") (pin "41") (pinfunction "PF0(ADC0)_41") (pintype "bidirectional"))
    )
    (net (code "104") (name "unconnected-(IC8-PF1(ADC1)-Pad40)") (class "Default")
      (node (ref "IC8") (pin "40") (pinfunction "PF1(ADC1)_40") (pintype "bidirectional"))
    )
    (net (code "105") (name "unconnected-(IC8-PF4(ADC4{slash}TCK)-Pad39)") (class "Default")
      (node (ref "IC8") (pin "39") (pinfunction "PF4(ADC4/TCK)_39") (pintype "bidirectional"))
    )
    (net (code "106") (name "unconnected-(IC8-PF5(ADC5{slash}TMS)-Pad38)") (class "Default")
      (node (ref "IC8") (pin "38") (pinfunction "PF5(ADC5/TMS)_38") (pintype "bidirectional"))
    )
    (net (code "107") (name "unconnected-(IC8-PF6(ADC6{slash}TDO)-Pad37)") (class "Default")
      (node (ref "IC8") (pin "37") (pinfunction "PF6(ADC6/TDO)_37") (pintype "bidirectional"))
    )
    (net (code "108") (name "unconnected-(IC8-PF7(ADC7(TDI)-Pad36)") (class "Default")
      (node (ref "IC8") (pin "36") (pinfunction "PF7(ADC7(TDI)_36") (pintype "bidirectional"))
    )
    (net (code "109") (name "unconnected-(JK1-PadRSH)") (class "Default")
      (node (ref "JK1") (pin "RSH") (pinfunction "RSH_RSH") (pintype "bidirectional"))
    )
    (net (code "110") (name "unconnected-(JK2-PadRSH)") (class "Default")
      (node (ref "JK2") (pin "RSH") (pinfunction "RSH_RSH") (pintype "bidirectional"))
    )
    (net (code "111") (name "unconnected-(JK3-PadRSH)") (class "Default")
      (node (ref "JK3") (pin "RSH") (pinfunction "RSH_RSH") (pintype "bidirectional"))
    )
    (net (code "112") (name "unconnected-(JK4-PadRSH)") (class "Default")
      (node (ref "JK4") (pin "RSH") (pinfunction "RSH_RSH") (pintype "bidirectional"))
    )
    (net (code "113") (name "unconnected-(U$1-DIO0-Pad20)") (class "Default")
      (node (ref "U$1") (pin "20") (pinfunction "DIO0_20") (pintype "bidirectional"))
    )
    (net (code "114") (name "unconnected-(U$1-DIO1-Pad19)") (class "Default")
      (node (ref "U$1") (pin "19") (pinfunction "DIO1_19") (pintype "bidirectional"))
    )
    (net (code "115") (name "unconnected-(U$1-DIO2-Pad18)") (class "Default")
      (node (ref "U$1") (pin "18") (pinfunction "DIO2_18") (pintype "bidirectional"))
    )
    (net (code "116") (name "unconnected-(U$1-DIO3-Pad17)") (class "Default")
      (node (ref "U$1") (pin "17") (pinfunction "DIO3_17") (pintype "bidirectional"))
    )
    (net (code "117") (name "unconnected-(U$1-DIO4-Pad11)") (class "Default")
      (node (ref "U$1") (pin "11") (pinfunction "DIO4_11") (pintype "bidirectional"))
    )
    (net (code "118") (name "unconnected-(U$1-DIO9-Pad13)") (class "Default")
      (node (ref "U$1") (pin "13") (pinfunction "DIO9_13") (pintype "bidirectional"))
    )
    (net (code "119") (name "unconnected-(U$1-DIO11-Pad7)") (class "Default")
      (node (ref "U$1") (pin "7") (pinfunction "DIO11_7") (pintype "bidirectional"))
    )
    (net (code "120") (name "unconnected-(U$1-DIO12-Pad4)") (class "Default")
      (node (ref "U$1") (pin "4") (pinfunction "DIO12_4") (pintype "bidirectional"))
    )
    (net (code "121") (name "unconnected-(U$1-RES-Pad8)") (class "Default")
      (node (ref "U$1") (pin "8") (pinfunction "RES_8") (pintype "bidirectional"))
    )
    (net (code "122") (name "unconnected-(U$1-RES-Pad14)") (class "Default")
      (node (ref "U$1") (pin "14") (pinfunction "RES_14") (pintype "bidirectional"))
    )
  )
)
